# QuadOPTOascii.net
KiCad netlist of a schematic drawn in Altium Designer
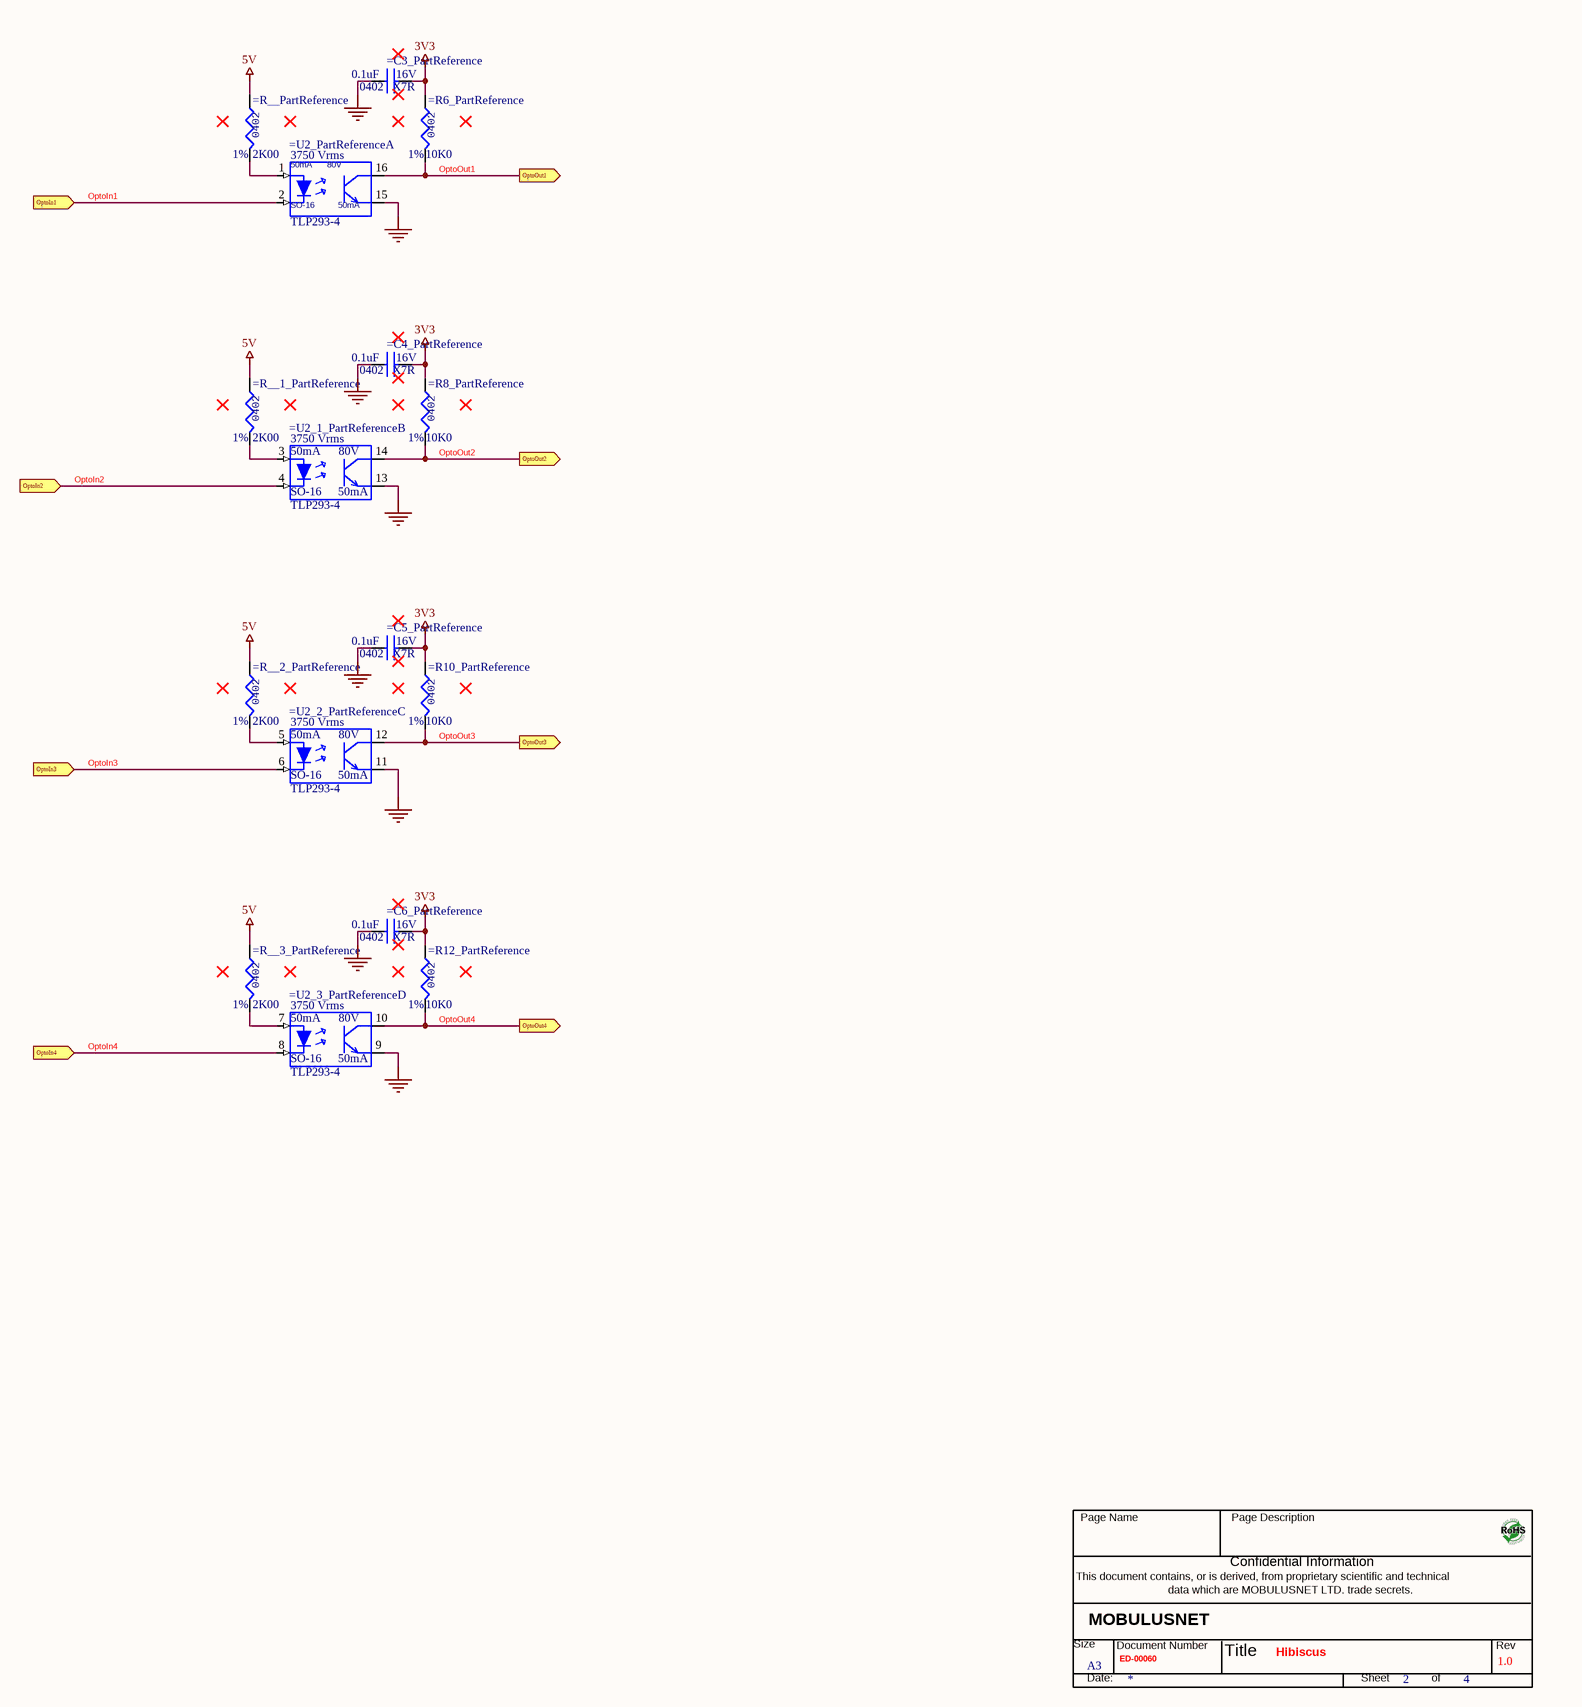
[diagram p0: QuadOPTOascii.SchDoc]

(export (version "E")
  (design (tool "Eeschema 10.0.6"))
  (components
    (comp (ref "*")
      (value "MobulusTitleBlock")
      (fields
        (field (name "TITLE") "Hibiscus")
        (field (name "REVCODE") "1.0")
        (field (name "PAGE SIZE") "A3")
        (field (name "PAGE NUMBER") "2")
        (field (name "PAGE COUNT") "4")
        (field (name "DOC") "ED-00060")
      )
      (libsource (lib "*") (part "MobulusTitleBlock"))
    )
    (comp (ref "=C3_PartReference")
      (value "0.1uF")
      (footprint "0402")
      (description "CAP_CER_0.1uF_16V_X7R_0402")
      (fields
        (field (name "VOLTAGE") "16V")
        (field (name "PART NUMBER") "CC0402KRX7R7BB104")
        (field (name "PCBFOOTPRINT") "0402   X7R")
        (field (name "MFG") "Yageo")
      )
      (libsource (lib "*") (part "CAP0402_0.1uF 16V"))
    )
    (comp (ref "=C4_PartReference")
      (value "0.1uF")
      (footprint "0402")
      (description "CAP_CER_0.1uF_16V_X7R_0402")
      (fields
        (field (name "VOLTAGE") "16V")
        (field (name "PART NUMBER") "CC0402KRX7R7BB104")
        (field (name "PCBFOOTPRINT") "0402   X7R")
        (field (name "MFG") "Yageo")
      )
      (libsource (lib "*") (part "CAP0402_0.1uF 16V"))
    )
    (comp (ref "=C5_PartReference")
      (value "0.1uF")
      (footprint "0402")
      (description "CAP_CER_0.1uF_16V_X7R_0402")
      (fields
        (field (name "VOLTAGE") "16V")
        (field (name "PART NUMBER") "CC0402KRX7R7BB104")
        (field (name "PCBFOOTPRINT") "0402   X7R")
        (field (name "MFG") "Yageo")
      )
      (libsource (lib "*") (part "CAP0402_0.1uF 16V"))
    )
    (comp (ref "=C6_PartReference")
      (value "0.1uF")
      (footprint "0402")
      (description "CAP_CER_0.1uF_16V_X7R_0402")
      (fields
        (field (name "VOLTAGE") "16V")
        (field (name "PART NUMBER") "CC0402KRX7R7BB104")
        (field (name "PCBFOOTPRINT") "0402   X7R")
        (field (name "MFG") "Yageo")
      )
      (libsource (lib "*") (part "CAP0402_0.1uF 16V"))
    )
    (comp (ref "=R6_PartReference")
      (value "10K0")
      (footprint "0402")
      (description "RES SMD 10K OHM 1% 1/16W 0402")
      (fields
        (field (name "TOLERANCE") "1%")
        (field (name "POWER") "1/16W")
        (field (name "PART NUMBER") "RC0402FR-0710KL")
      )
      (libsource (lib "*") (part "R0402_10K0_1%"))
    )
    (comp (ref "=R8_PartReference")
      (value "10K0")
      (footprint "0402")
      (description "RES SMD 10K OHM 1% 1/16W 0402")
      (fields
        (field (name "TOLERANCE") "1%")
        (field (name "POWER") "1/16W")
        (field (name "PART NUMBER") "RC0402FR-0710KL")
      )
      (libsource (lib "*") (part "R0402_10K0_1%"))
    )
    (comp (ref "=R10_PartReference")
      (value "10K0")
      (footprint "0402")
      (description "RES SMD 10K OHM 1% 1/16W 0402")
      (fields
        (field (name "TOLERANCE") "1%")
        (field (name "POWER") "1/16W")
        (field (name "PART NUMBER") "RC0402FR-0710KL")
      )
      (libsource (lib "*") (part "R0402_10K0_1%"))
    )
    (comp (ref "=R12_PartReference")
      (value "10K0")
      (footprint "0402")
      (description "RES SMD 10K OHM 1% 1/16W 0402")
      (fields
        (field (name "TOLERANCE") "1%")
        (field (name "POWER") "1/16W")
        (field (name "PART NUMBER") "RC0402FR-0710KL")
      )
      (libsource (lib "*") (part "R0402_10K0_1%"))
    )
    (comp (ref "=R__1_PartReference")
      (value "2K00")
      (footprint "0402")
      (description "RES SMD 2K OHM 1% 1/16W 0402")
      (fields
        (field (name "TOLERANCE") "1%")
        (field (name "POWER") "1/16W")
        (field (name "PART NUMBER") "RC0402FR-072KL")
      )
      (libsource (lib "*") (part "R0402_2K00_1%"))
    )
    (comp (ref "=R__2_PartReference")
      (value "2K00")
      (footprint "0402")
      (description "RES SMD 2K OHM 1% 1/16W 0402")
      (fields
        (field (name "TOLERANCE") "1%")
        (field (name "POWER") "1/16W")
        (field (name "PART NUMBER") "RC0402FR-072KL")
      )
      (libsource (lib "*") (part "R0402_2K00_1%"))
    )
    (comp (ref "=R__3_PartReference")
      (value "2K00")
      (footprint "0402")
      (description "RES SMD 2K OHM 1% 1/16W 0402")
      (fields
        (field (name "TOLERANCE") "1%")
        (field (name "POWER") "1/16W")
        (field (name "PART NUMBER") "RC0402FR-072KL")
      )
      (libsource (lib "*") (part "R0402_2K00_1%"))
    )
    (comp (ref "=R__PartReference")
      (value "2K00")
      (footprint "0402")
      (description "RES SMD 2K OHM 1% 1/16W 0402")
      (fields
        (field (name "TOLERANCE") "1%")
        (field (name "POWER") "1/16W")
        (field (name "PART NUMBER") "RC0402FR-072KL")
      )
      (libsource (lib "*") (part "R0402_2K00_1%"))
    )
    (comp (ref "=U2_1_PartReference")
      (value "TLP293-4")
      (footprint "SO-16")
      (description "OPTOISOLATOR 3.75KV TRANS SO16")
      (fields
        (field (name "POWER") "50mA      80V")
        (field (name "PART NUMBER") "TLP293-4(V4,E")
        (field (name "MFG") "Toshiba Semiconductor and Storage")
        (field (name "ISO") "3750 Vrms")
        (field (name "CURRENT POWER") "50mA")
      )
      (libsource (lib "*") (part "TLP293-4"))
    )
    (comp (ref "=U2_2_PartReference")
      (value "TLP293-4")
      (footprint "SO-16")
      (description "OPTOISOLATOR 3.75KV TRANS SO16")
      (fields
        (field (name "POWER") "50mA      80V")
        (field (name "PART NUMBER") "TLP293-4(V4,E")
        (field (name "MFG") "Toshiba Semiconductor and Storage")
        (field (name "ISO") "3750 Vrms")
        (field (name "CURRENT POWER") "50mA")
      )
      (libsource (lib "*") (part "TLP293-4"))
    )
    (comp (ref "=U2_3_PartReference")
      (value "TLP293-4")
      (footprint "SO-16")
      (description "OPTOISOLATOR 3.75KV TRANS SO16")
      (fields
        (field (name "POWER") "50mA      80V")
        (field (name "PART NUMBER") "TLP293-4(V4,E")
        (field (name "MFG") "Toshiba Semiconductor and Storage")
        (field (name "ISO") "3750 Vrms")
        (field (name "CURRENT POWER") "50mA")
      )
      (libsource (lib "*") (part "TLP293-4"))
    )
    (comp (ref "=U2_PartReference")
      (value "TLP293-4")
      (footprint "SO-16")
      (description "OPTOISOLATOR 3.75KV TRANS SO16")
      (fields
        (field (name "POWER") "50mA      80V")
        (field (name "PART NUMBER") "TLP293-4(V4,E")
        (field (name "MFG") "Toshiba Semiconductor and Storage")
        (field (name "ISO") "3750 Vrms")
        (field (name "CURRENT POWER") "50mA")
      )
      (libsource (lib "*") (part "TLP293-4"))
    )
  )
  (nets
    (net (code "1") (name "/OptoIn1") (class "Default")
      (node (ref "=U2_PartReference") (pin "2") (pinfunction "K_2") (pintype "input"))
    )
    (net (code "2") (name "/OptoIn2") (class "Default")
      (node (ref "=U2_1_PartReference") (pin "4") (pinfunction "K_4") (pintype "input"))
    )
    (net (code "3") (name "/OptoIn3") (class "Default")
      (node (ref "=U2_2_PartReference") (pin "6") (pinfunction "K_6") (pintype "input"))
    )
    (net (code "4") (name "/OptoIn4") (class "Default")
      (node (ref "=U2_3_PartReference") (pin "8") (pinfunction "K_8") (pintype "input"))
    )
    (net (code "5") (name "/OptoOut1") (class "Default")
      (node (ref "=R6_PartReference") (pin "2") (pinfunction "2_2") (pintype "passive"))
      (node (ref "=U2_PartReference") (pin "16") (pinfunction "C_16") (pintype "open_collector"))
    )
    (net (code "6") (name "/OptoOut2") (class "Default")
      (node (ref "=R8_PartReference") (pin "2") (pinfunction "2_2") (pintype "passive"))
      (node (ref "=U2_1_PartReference") (pin "14") (pinfunction "C_14") (pintype "open_collector"))
    )
    (net (code "7") (name "/OptoOut3") (class "Default")
      (node (ref "=R10_PartReference") (pin "2") (pinfunction "2_2") (pintype "passive"))
      (node (ref "=U2_2_PartReference") (pin "12") (pinfunction "C_12") (pintype "open_collector"))
    )
    (net (code "8") (name "/OptoOut4") (class "Default")
      (node (ref "=R12_PartReference") (pin "2") (pinfunction "2_2") (pintype "passive"))
      (node (ref "=U2_3_PartReference") (pin "10") (pinfunction "C_10") (pintype "open_collector"))
    )
    (net (code "9") (name "3V3") (class "Default")
      (node (ref "=C3_PartReference") (pin "2") (pinfunction "2_2") (pintype "passive"))
      (node (ref "=C4_PartReference") (pin "2") (pinfunction "2_2") (pintype "passive"))
      (node (ref "=C5_PartReference") (pin "2") (pinfunction "2_2") (pintype "passive"))
      (node (ref "=C6_PartReference") (pin "2") (pinfunction "2_2") (pintype "passive"))
      (node (ref "=R10_PartReference") (pin "1") (pinfunction "1_1") (pintype "passive"))
      (node (ref "=R12_PartReference") (pin "1") (pinfunction "1_1") (pintype "passive"))
      (node (ref "=R6_PartReference") (pin "1") (pinfunction "1_1") (pintype "passive"))
      (node (ref "=R8_PartReference") (pin "1") (pinfunction "1_1") (pintype "passive"))
    )
    (net (code "10") (name "5V") (class "Default")
      (node (ref "=R__1_PartReference") (pin "1") (pinfunction "1_1") (pintype "passive"))
      (node (ref "=R__2_PartReference") (pin "1") (pinfunction "1_1") (pintype "passive"))
      (node (ref "=R__3_PartReference") (pin "1") (pinfunction "1_1") (pintype "passive"))
      (node (ref "=R__PartReference") (pin "1") (pinfunction "1_1") (pintype "passive"))
    )
    (net (code "11") (name "GND") (class "Default")
      (node (ref "=C3_PartReference") (pin "1") (pinfunction "1_1") (pintype "passive"))
      (node (ref "=C4_PartReference") (pin "1") (pinfunction "1_1") (pintype "passive"))
      (node (ref "=C5_PartReference") (pin "1") (pinfunction "1_1") (pintype "passive"))
      (node (ref "=C6_PartReference") (pin "1") (pinfunction "1_1") (pintype "passive"))
      (node (ref "=U2_1_PartReference") (pin "13") (pinfunction "E_13") (pintype "open_emitter"))
      (node (ref "=U2_2_PartReference") (pin "11") (pinfunction "E_11") (pintype "open_emitter"))
      (node (ref "=U2_3_PartReference") (pin "9") (pinfunction "E_9") (pintype "open_emitter"))
      (node (ref "=U2_PartReference") (pin "15") (pinfunction "E_15") (pintype "open_emitter"))
    )
    (net (code "12") (name "Net-(=U2_1_PartReferenceB-A)") (class "Default")
      (node (ref "=R__1_PartReference") (pin "2") (pinfunction "2_2") (pintype "passive"))
      (node (ref "=U2_1_PartReference") (pin "3") (pinfunction "A_3") (pintype "input"))
    )
    (net (code "13") (name "Net-(=U2_2_PartReferenceC-A)") (class "Default")
      (node (ref "=R__2_PartReference") (pin "2") (pinfunction "2_2") (pintype "passive"))
      (node (ref "=U2_2_PartReference") (pin "5") (pinfunction "A_5") (pintype "input"))
    )
    (net (code "14") (name "Net-(=U2_3_PartReferenceD-A)") (class "Default")
      (node (ref "=R__3_PartReference") (pin "2") (pinfunction "2_2") (pintype "passive"))
      (node (ref "=U2_3_PartReference") (pin "7") (pinfunction "A_7") (pintype "input"))
    )
    (net (code "15") (name "Net-(=U2_PartReferenceA-A)") (class "Default")
      (node (ref "=R__PartReference") (pin "2") (pinfunction "2_2") (pintype "passive"))
      (node (ref "=U2_PartReference") (pin "1") (pinfunction "A_1") (pintype "input"))
    )
  )
)
